# TensoSensor.net
KiCad netlist of a schematic drawn in Altium Designer
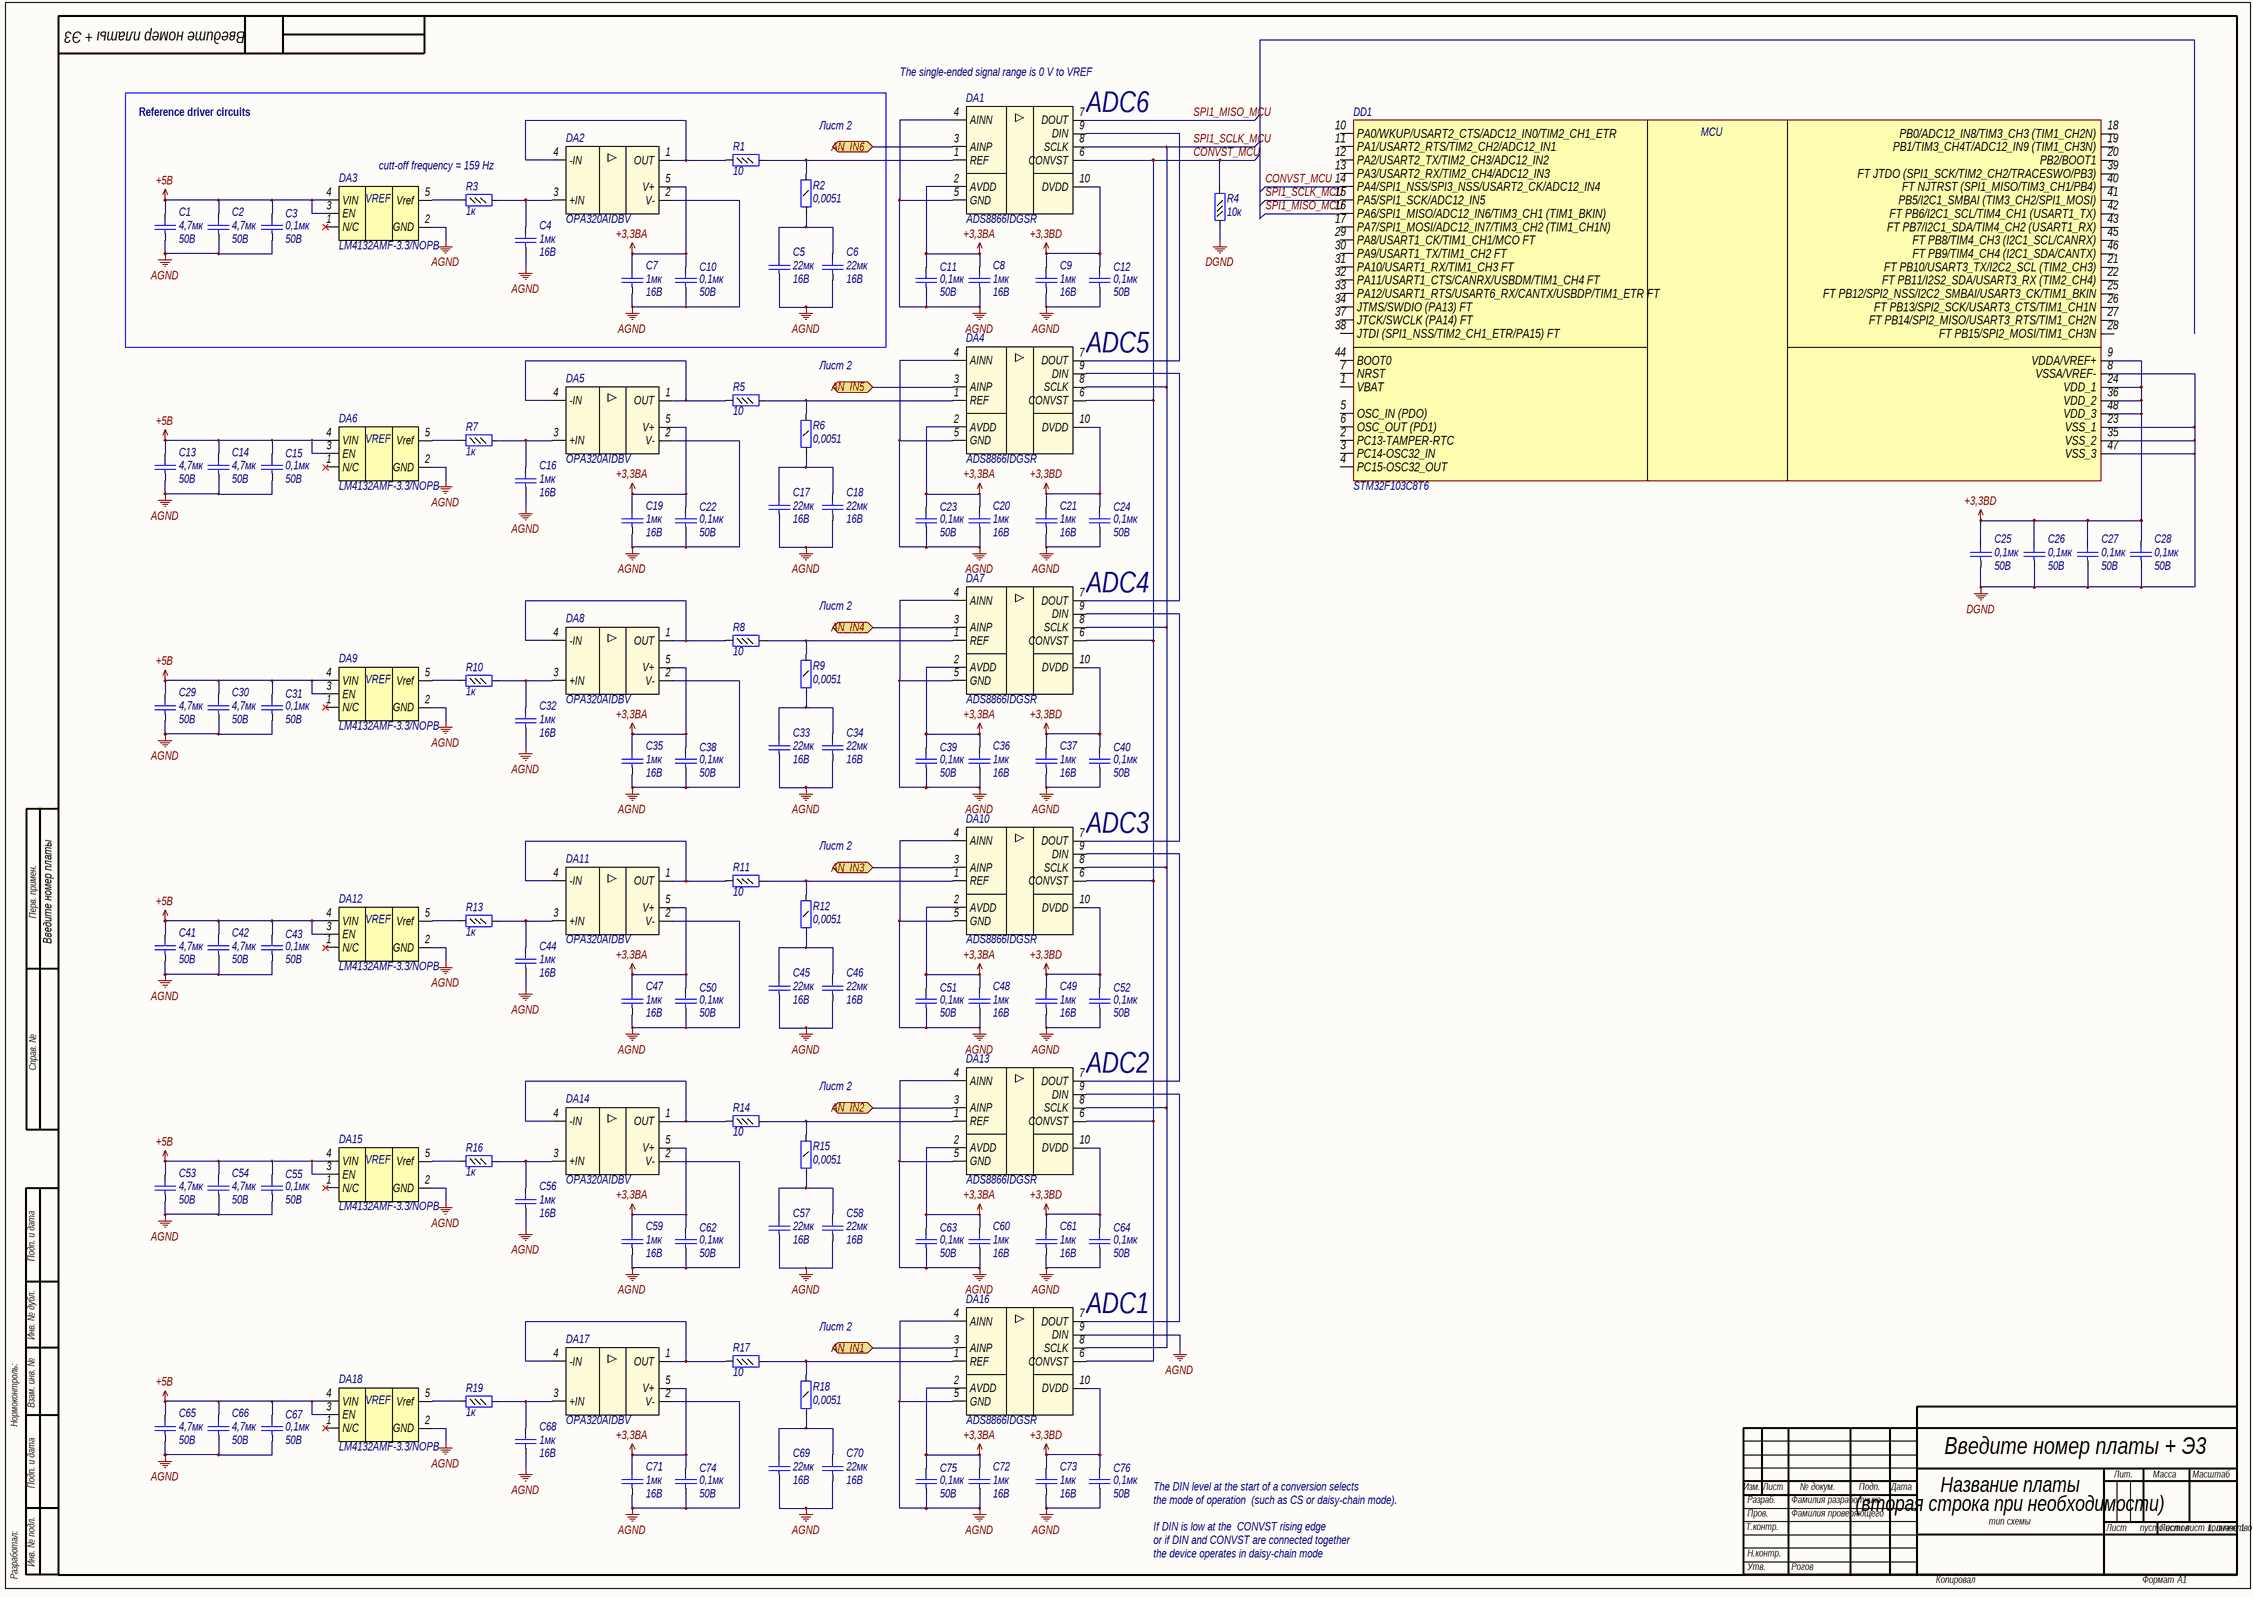
[diagram p0: TensoSensor.SchDoc]

(export (version "E")
  (design (tool "Eeschema 10.0.6"))
  (components
    (comp (ref "C1")
      (value "4,7мк")
      (footprint "C0805")
      (description "Конденсатор")
      (fields (field (name "VOLTAGE") "50В") (field (name "PART NUMBER") "GRM21BZ71H475KE15L"))
      (libsource (lib "MOP44") (part "Capacitor"))
    )
    (comp (ref "C2")
      (value "4,7мк")
      (footprint "C0805")
      (description "Конденсатор")
      (fields (field (name "VOLTAGE") "50В") (field (name "PART NUMBER") "GRM21BZ71H475KE15L"))
      (libsource (lib "MOP44") (part "Capacitor"))
    )
    (comp (ref "C3")
      (value "0,1мк")
      (footprint "C0603")
      (description "Конденсатор")
      (fields (field (name "VOLTAGE") "50B") (field (name "PART NUMBER") "GRM188R71H104KA93D"))
      (libsource (lib "MOP44") (part "Capacitor"))
    )
    (comp (ref "C4")
      (value "1мк")
      (footprint "C0603")
      (description "Конденсатор")
      (fields (field (name "VOLTAGE") "16B") (field (name "PART NUMBER") "GRM188R71C105KA12D**"))
      (libsource (lib "MOP44") (part "Capacitor"))
    )
    (comp (ref "C5")
      (value "22мк")
      (footprint "C1210")
      (description "Конденсатор")
      (fields (field (name "VOLTAGE") "16B") (field (name "PART NUMBER") "C3225X7R1C226M"))
      (libsource (lib "MOP44") (part "Capacitor"))
    )
    (comp (ref "C6")
      (value "22мк")
      (footprint "C1210")
      (description "Конденсатор")
      (fields (field (name "VOLTAGE") "16B") (field (name "PART NUMBER") "C3225X7R1C226M"))
      (libsource (lib "MOP44") (part "Capacitor"))
    )
    (comp (ref "C7")
      (value "1мк")
      (footprint "C0603")
      (description "Конденсатор")
      (fields (field (name "VOLTAGE") "16B") (field (name "PART NUMBER") "GRM188R71C105KA12D**"))
      (libsource (lib "MOP44") (part "Capacitor"))
    )
    (comp (ref "C8")
      (value "1мк")
      (footprint "C0603")
      (description "Конденсатор")
      (fields (field (name "VOLTAGE") "16B") (field (name "PART NUMBER") "GRM188R71C105KA12D**"))
      (libsource (lib "MOP44") (part "Capacitor"))
    )
    (comp (ref "C9")
      (value "1мк")
      (footprint "C0603")
      (description "Конденсатор")
      (fields (field (name "VOLTAGE") "16B") (field (name "PART NUMBER") "GRM188R71C105KA12D**"))
      (libsource (lib "MOP44") (part "Capacitor"))
    )
    (comp (ref "C10")
      (value "0,1мк")
      (footprint "C0603")
      (description "Конденсатор")
      (fields (field (name "VOLTAGE") "50B") (field (name "PART NUMBER") "GRM188R71H104KA93D"))
      (libsource (lib "MOP44") (part "Capacitor"))
    )
    (comp (ref "C11")
      (value "0,1мк")
      (footprint "C0603")
      (description "Конденсатор")
      (fields (field (name "VOLTAGE") "50B") (field (name "PART NUMBER") "GRM188R71H104KA93D"))
      (libsource (lib "MOP44") (part "Capacitor"))
    )
    (comp (ref "C12")
      (value "0,1мк")
      (footprint "C0603")
      (description "Конденсатор")
      (fields (field (name "VOLTAGE") "50B") (field (name "PART NUMBER") "GRM188R71H104KA93D"))
      (libsource (lib "MOP44") (part "Capacitor"))
    )
    (comp (ref "C13")
      (value "4,7мк")
      (footprint "C0805")
      (description "Конденсатор")
      (fields (field (name "VOLTAGE") "50В") (field (name "PART NUMBER") "GRM21BZ71H475KE15L"))
      (libsource (lib "MOP44") (part "Capacitor"))
    )
    (comp (ref "C14")
      (value "4,7мк")
      (footprint "C0805")
      (description "Конденсатор")
      (fields (field (name "VOLTAGE") "50В") (field (name "PART NUMBER") "GRM21BZ71H475KE15L"))
      (libsource (lib "MOP44") (part "Capacitor"))
    )
    (comp (ref "C15")
      (value "0,1мк")
      (footprint "C0603")
      (description "Конденсатор")
      (fields (field (name "VOLTAGE") "50B") (field (name "PART NUMBER") "GRM188R71H104KA93D"))
      (libsource (lib "MOP44") (part "Capacitor"))
    )
    (comp (ref "C16")
      (value "1мк")
      (footprint "C0603")
      (description "Конденсатор")
      (fields (field (name "VOLTAGE") "16B") (field (name "PART NUMBER") "GRM188R71C105KA12D**"))
      (libsource (lib "MOP44") (part "Capacitor"))
    )
    (comp (ref "C17")
      (value "22мк")
      (footprint "C1210")
      (description "Конденсатор")
      (fields (field (name "VOLTAGE") "16B") (field (name "PART NUMBER") "C3225X7R1C226M"))
      (libsource (lib "MOP44") (part "Capacitor"))
    )
    (comp (ref "C18")
      (value "22мк")
      (footprint "C1210")
      (description "Конденсатор")
      (fields (field (name "VOLTAGE") "16B") (field (name "PART NUMBER") "C3225X7R1C226M"))
      (libsource (lib "MOP44") (part "Capacitor"))
    )
    (comp (ref "C19")
      (value "1мк")
      (footprint "C0603")
      (description "Конденсатор")
      (fields (field (name "VOLTAGE") "16B") (field (name "PART NUMBER") "GRM188R71C105KA12D**"))
      (libsource (lib "MOP44") (part "Capacitor"))
    )
    (comp (ref "C20")
      (value "1мк")
      (footprint "C0603")
      (description "Конденсатор")
      (fields (field (name "VOLTAGE") "16B") (field (name "PART NUMBER") "GRM188R71C105KA12D**"))
      (libsource (lib "MOP44") (part "Capacitor"))
    )
    (comp (ref "C21")
      (value "1мк")
      (footprint "C0603")
      (description "Конденсатор")
      (fields (field (name "VOLTAGE") "16B") (field (name "PART NUMBER") "GRM188R71C105KA12D**"))
      (libsource (lib "MOP44") (part "Capacitor"))
    )
    (comp (ref "C22")
      (value "0,1мк")
      (footprint "C0603")
      (description "Конденсатор")
      (fields (field (name "VOLTAGE") "50B") (field (name "PART NUMBER") "GRM188R71H104KA93D"))
      (libsource (lib "MOP44") (part "Capacitor"))
    )
    (comp (ref "C23")
      (value "0,1мк")
      (footprint "C0603")
      (description "Конденсатор")
      (fields (field (name "VOLTAGE") "50B") (field (name "PART NUMBER") "GRM188R71H104KA93D"))
      (libsource (lib "MOP44") (part "Capacitor"))
    )
    (comp (ref "C24")
      (value "0,1мк")
      (footprint "C0603")
      (description "Конденсатор")
      (fields (field (name "VOLTAGE") "50B") (field (name "PART NUMBER") "GRM188R71H104KA93D"))
      (libsource (lib "MOP44") (part "Capacitor"))
    )
    (comp (ref "C25")
      (value "0,1мк")
      (footprint "C0603")
      (description "Конденсатор")
      (fields (field (name "VOLTAGE") "50B") (field (name "PART NUMBER") "GRM188R71H104KA93D"))
      (libsource (lib "MOP44") (part "Capacitor"))
    )
    (comp (ref "C26")
      (value "0,1мк")
      (footprint "C0603")
      (description "Конденсатор")
      (fields (field (name "VOLTAGE") "50B") (field (name "PART NUMBER") "GRM188R71H104KA93D"))
      (libsource (lib "MOP44") (part "Capacitor"))
    )
    (comp (ref "C27")
      (value "0,1мк")
      (footprint "C0603")
      (description "Конденсатор")
      (fields (field (name "VOLTAGE") "50B") (field (name "PART NUMBER") "GRM188R71H104KA93D"))
      (libsource (lib "MOP44") (part "Capacitor"))
    )
    (comp (ref "C28")
      (value "0,1мк")
      (footprint "C0603")
      (description "Конденсатор")
      (fields (field (name "VOLTAGE") "50B") (field (name "PART NUMBER") "GRM188R71H104KA93D"))
      (libsource (lib "MOP44") (part "Capacitor"))
    )
    (comp (ref "C29")
      (value "4,7мк")
      (footprint "C0805")
      (description "Конденсатор")
      (fields (field (name "VOLTAGE") "50В") (field (name "PART NUMBER") "GRM21BZ71H475KE15L"))
      (libsource (lib "MOP44") (part "Capacitor"))
    )
    (comp (ref "C30")
      (value "4,7мк")
      (footprint "C0805")
      (description "Конденсатор")
      (fields (field (name "VOLTAGE") "50В") (field (name "PART NUMBER") "GRM21BZ71H475KE15L"))
      (libsource (lib "MOP44") (part "Capacitor"))
    )
    (comp (ref "C31")
      (value "0,1мк")
      (footprint "C0603")
      (description "Конденсатор")
      (fields (field (name "VOLTAGE") "50B") (field (name "PART NUMBER") "GRM188R71H104KA93D"))
      (libsource (lib "MOP44") (part "Capacitor"))
    )
    (comp (ref "C32")
      (value "1мк")
      (footprint "C0603")
      (description "Конденсатор")
      (fields (field (name "VOLTAGE") "16B") (field (name "PART NUMBER") "GRM188R71C105KA12D**"))
      (libsource (lib "MOP44") (part "Capacitor"))
    )
    (comp (ref "C33")
      (value "22мк")
      (footprint "C1210")
      (description "Конденсатор")
      (fields (field (name "VOLTAGE") "16B") (field (name "PART NUMBER") "C3225X7R1C226M"))
      (libsource (lib "MOP44") (part "Capacitor"))
    )
    (comp (ref "C34")
      (value "22мк")
      (footprint "C1210")
      (description "Конденсатор")
      (fields (field (name "VOLTAGE") "16B") (field (name "PART NUMBER") "C3225X7R1C226M"))
      (libsource (lib "MOP44") (part "Capacitor"))
    )
    (comp (ref "C35")
      (value "1мк")
      (footprint "C0603")
      (description "Конденсатор")
      (fields (field (name "VOLTAGE") "16B") (field (name "PART NUMBER") "GRM188R71C105KA12D**"))
      (libsource (lib "MOP44") (part "Capacitor"))
    )
    (comp (ref "C36")
      (value "1мк")
      (footprint "C0603")
      (description "Конденсатор")
      (fields (field (name "VOLTAGE") "16B") (field (name "PART NUMBER") "GRM188R71C105KA12D**"))
      (libsource (lib "MOP44") (part "Capacitor"))
    )
    (comp (ref "C37")
      (value "1мк")
      (footprint "C0603")
      (description "Конденсатор")
      (fields (field (name "VOLTAGE") "16B") (field (name "PART NUMBER") "GRM188R71C105KA12D**"))
      (libsource (lib "MOP44") (part "Capacitor"))
    )
    (comp (ref "C38")
      (value "0,1мк")
      (footprint "C0603")
      (description "Конденсатор")
      (fields (field (name "VOLTAGE") "50B") (field (name "PART NUMBER") "GRM188R71H104KA93D"))
      (libsource (lib "MOP44") (part "Capacitor"))
    )
    (comp (ref "C39")
      (value "0,1мк")
      (footprint "C0603")
      (description "Конденсатор")
      (fields (field (name "VOLTAGE") "50B") (field (name "PART NUMBER") "GRM188R71H104KA93D"))
      (libsource (lib "MOP44") (part "Capacitor"))
    )
    (comp (ref "C40")
      (value "0,1мк")
      (footprint "C0603")
      (description "Конденсатор")
      (fields (field (name "VOLTAGE") "50B") (field (name "PART NUMBER") "GRM188R71H104KA93D"))
      (libsource (lib "MOP44") (part "Capacitor"))
    )
    (comp (ref "C41")
      (value "4,7мк")
      (footprint "C0805")
      (description "Конденсатор")
      (fields (field (name "VOLTAGE") "50В") (field (name "PART NUMBER") "GRM21BZ71H475KE15L"))
      (libsource (lib "MOP44") (part "Capacitor"))
    )
    (comp (ref "C42")
      (value "4,7мк")
      (footprint "C0805")
      (description "Конденсатор")
      (fields (field (name "VOLTAGE") "50В") (field (name "PART NUMBER") "GRM21BZ71H475KE15L"))
      (libsource (lib "MOP44") (part "Capacitor"))
    )
    (comp (ref "C43")
      (value "0,1мк")
      (footprint "C0603")
      (description "Конденсатор")
      (fields (field (name "VOLTAGE") "50B") (field (name "PART NUMBER") "GRM188R71H104KA93D"))
      (libsource (lib "MOP44") (part "Capacitor"))
    )
    (comp (ref "C44")
      (value "1мк")
      (footprint "C0603")
      (description "Конденсатор")
      (fields (field (name "VOLTAGE") "16B") (field (name "PART NUMBER") "GRM188R71C105KA12D**"))
      (libsource (lib "MOP44") (part "Capacitor"))
    )
    (comp (ref "C45")
      (value "22мк")
      (footprint "C1210")
      (description "Конденсатор")
      (fields (field (name "VOLTAGE") "16B") (field (name "PART NUMBER") "C3225X7R1C226M"))
      (libsource (lib "MOP44") (part "Capacitor"))
    )
    (comp (ref "C46")
      (value "22мк")
      (footprint "C1210")
      (description "Конденсатор")
      (fields (field (name "VOLTAGE") "16B") (field (name "PART NUMBER") "C3225X7R1C226M"))
      (libsource (lib "MOP44") (part "Capacitor"))
    )
    (comp (ref "C47")
      (value "1мк")
      (footprint "C0603")
      (description "Конденсатор")
      (fields (field (name "VOLTAGE") "16B") (field (name "PART NUMBER") "GRM188R71C105KA12D**"))
      (libsource (lib "MOP44") (part "Capacitor"))
    )
    (comp (ref "C48")
      (value "1мк")
      (footprint "C0603")
      (description "Конденсатор")
      (fields (field (name "VOLTAGE") "16B") (field (name "PART NUMBER") "GRM188R71C105KA12D**"))
      (libsource (lib "MOP44") (part "Capacitor"))
    )
    (comp (ref "C49")
      (value "1мк")
      (footprint "C0603")
      (description "Конденсатор")
      (fields (field (name "VOLTAGE") "16B") (field (name "PART NUMBER") "GRM188R71C105KA12D**"))
      (libsource (lib "MOP44") (part "Capacitor"))
    )
    (comp (ref "C50")
      (value "0,1мк")
      (footprint "C0603")
      (description "Конденсатор")
      (fields (field (name "VOLTAGE") "50B") (field (name "PART NUMBER") "GRM188R71H104KA93D"))
      (libsource (lib "MOP44") (part "Capacitor"))
    )
    (comp (ref "C51")
      (value "0,1мк")
      (footprint "C0603")
      (description "Конденсатор")
      (fields (field (name "VOLTAGE") "50B") (field (name "PART NUMBER") "GRM188R71H104KA93D"))
      (libsource (lib "MOP44") (part "Capacitor"))
    )
    (comp (ref "C52")
      (value "0,1мк")
      (footprint "C0603")
      (description "Конденсатор")
      (fields (field (name "VOLTAGE") "50B") (field (name "PART NUMBER") "GRM188R71H104KA93D"))
      (libsource (lib "MOP44") (part "Capacitor"))
    )
    (comp (ref "C53")
      (value "4,7мк")
      (footprint "C0805")
      (description "Конденсатор")
      (fields (field (name "VOLTAGE") "50В") (field (name "PART NUMBER") "GRM21BZ71H475KE15L"))
      (libsource (lib "MOP44") (part "Capacitor"))
    )
    (comp (ref "C54")
      (value "4,7мк")
      (footprint "C0805")
      (description "Конденсатор")
      (fields (field (name "VOLTAGE") "50В") (field (name "PART NUMBER") "GRM21BZ71H475KE15L"))
      (libsource (lib "MOP44") (part "Capacitor"))
    )
    (comp (ref "C55")
      (value "0,1мк")
      (footprint "C0603")
      (description "Конденсатор")
      (fields (field (name "VOLTAGE") "50B") (field (name "PART NUMBER") "GRM188R71H104KA93D"))
      (libsource (lib "MOP44") (part "Capacitor"))
    )
    (comp (ref "C56")
      (value "1мк")
      (footprint "C0603")
      (description "Конденсатор")
      (fields (field (name "VOLTAGE") "16B") (field (name "PART NUMBER") "GRM188R71C105KA12D**"))
      (libsource (lib "MOP44") (part "Capacitor"))
    )
    (comp (ref "C57")
      (value "22мк")
      (footprint "C1210")
      (description "Конденсатор")
      (fields (field (name "VOLTAGE") "16B") (field (name "PART NUMBER") "C3225X7R1C226M"))
      (libsource (lib "MOP44") (part "Capacitor"))
    )
    (comp (ref "C58")
      (value "22мк")
      (footprint "C1210")
      (description "Конденсатор")
      (fields (field (name "VOLTAGE") "16B") (field (name "PART NUMBER") "C3225X7R1C226M"))
      (libsource (lib "MOP44") (part "Capacitor"))
    )
    (comp (ref "C59")
      (value "1мк")
      (footprint "C0603")
      (description "Конденсатор")
      (fields (field (name "VOLTAGE") "16B") (field (name "PART NUMBER") "GRM188R71C105KA12D**"))
      (libsource (lib "MOP44") (part "Capacitor"))
    )
    (comp (ref "C60")
      (value "1мк")
      (footprint "C0603")
      (description "Конденсатор")
      (fields (field (name "VOLTAGE") "16B") (field (name "PART NUMBER") "GRM188R71C105KA12D**"))
      (libsource (lib "MOP44") (part "Capacitor"))
    )
    (comp (ref "C61")
      (value "1мк")
      (footprint "C0603")
      (description "Конденсатор")
      (fields (field (name "VOLTAGE") "16B") (field (name "PART NUMBER") "GRM188R71C105KA12D**"))
      (libsource (lib "MOP44") (part "Capacitor"))
    )
    (comp (ref "C62")
      (value "0,1мк")
      (footprint "C0603")
      (description "Конденсатор")
      (fields (field (name "VOLTAGE") "50B") (field (name "PART NUMBER") "GRM188R71H104KA93D"))
      (libsource (lib "MOP44") (part "Capacitor"))
    )
    (comp (ref "C63")
      (value "0,1мк")
      (footprint "C0603")
      (description "Конденсатор")
      (fields (field (name "VOLTAGE") "50B") (field (name "PART NUMBER") "GRM188R71H104KA93D"))
      (libsource (lib "MOP44") (part "Capacitor"))
    )
    (comp (ref "C64")
      (value "0,1мк")
      (footprint "C0603")
      (description "Конденсатор")
      (fields (field (name "VOLTAGE") "50B") (field (name "PART NUMBER") "GRM188R71H104KA93D"))
      (libsource (lib "MOP44") (part "Capacitor"))
    )
    (comp (ref "C65")
      (value "4,7мк")
      (footprint "C0805")
      (description "Конденсатор")
      (fields (field (name "VOLTAGE") "50В") (field (name "PART NUMBER") "GRM21BZ71H475KE15L"))
      (libsource (lib "MOP44") (part "Capacitor"))
    )
    (comp (ref "C66")
      (value "4,7мк")
      (footprint "C0805")
      (description "Конденсатор")
      (fields (field (name "VOLTAGE") "50В") (field (name "PART NUMBER") "GRM21BZ71H475KE15L"))
      (libsource (lib "MOP44") (part "Capacitor"))
    )
    (comp (ref "C67")
      (value "0,1мк")
      (footprint "C0603")
      (description "Конденсатор")
      (fields (field (name "VOLTAGE") "50B") (field (name "PART NUMBER") "GRM188R71H104KA93D"))
      (libsource (lib "MOP44") (part "Capacitor"))
    )
    (comp (ref "C68")
      (value "1мк")
      (footprint "C0603")
      (description "Конденсатор")
      (fields (field (name "VOLTAGE") "16B") (field (name "PART NUMBER") "GRM188R71C105KA12D**"))
      (libsource (lib "MOP44") (part "Capacitor"))
    )
    (comp (ref "C69")
      (value "22мк")
      (footprint "C1210")
      (description "Конденсатор")
      (fields (field (name "VOLTAGE") "16B") (field (name "PART NUMBER") "C3225X7R1C226M"))
      (libsource (lib "MOP44") (part "Capacitor"))
    )
    (comp (ref "C70")
      (value "22мк")
      (footprint "C1210")
      (description "Конденсатор")
      (fields (field (name "VOLTAGE") "16B") (field (name "PART NUMBER") "C3225X7R1C226M"))
      (libsource (lib "MOP44") (part "Capacitor"))
    )
    (comp (ref "C71")
      (value "1мк")
      (footprint "C0603")
      (description "Конденсатор")
      (fields (field (name "VOLTAGE") "16B") (field (name "PART NUMBER") "GRM188R71C105KA12D**"))
      (libsource (lib "MOP44") (part "Capacitor"))
    )
    (comp (ref "C72")
      (value "1мк")
      (footprint "C0603")
      (description "Конденсатор")
      (fields (field (name "VOLTAGE") "16B") (field (name "PART NUMBER") "GRM188R71C105KA12D**"))
      (libsource (lib "MOP44") (part "Capacitor"))
    )
    (comp (ref "C73")
      (value "1мк")
      (footprint "C0603")
      (description "Конденсатор")
      (fields (field (name "VOLTAGE") "16B") (field (name "PART NUMBER") "GRM188R71C105KA12D**"))
      (libsource (lib "MOP44") (part "Capacitor"))
    )
    (comp (ref "C74")
      (value "0,1мк")
      (footprint "C0603")
      (description "Конденсатор")
      (fields (field (name "VOLTAGE") "50B") (field (name "PART NUMBER") "GRM188R71H104KA93D"))
      (libsource (lib "MOP44") (part "Capacitor"))
    )
    (comp (ref "C75")
      (value "0,1мк")
      (footprint "C0603")
      (description "Конденсатор")
      (fields (field (name "VOLTAGE") "50B") (field (name "PART NUMBER") "GRM188R71H104KA93D"))
      (libsource (lib "MOP44") (part "Capacitor"))
    )
    (comp (ref "C76")
      (value "0,1мк")
      (footprint "C0603")
      (description "Конденсатор")
      (fields (field (name "VOLTAGE") "50B") (field (name "PART NUMBER") "GRM188R71H104KA93D"))
      (libsource (lib "MOP44") (part "Capacitor"))
    )
    (comp (ref "DA1")
      (value "ADS8866")
      (footprint "MSOP10")
      (description "100-kSPS, serial interface, micropower, miniature,  single-ended input, SAR")
      (fields (field (name "PART NUMBER") "ADS8866IDGSR"))
      (libsource (lib "MOP44") (part "ADS8866"))
    )
    (comp (ref "DA2")
      (value "OPA320")
      (footprint "SOT23-5")
      (description "Precision, 20-MHz, 0.9-pA, Low-Noise, RRIO")
      (fields (field (name "PART NUMBER") "OPA320AIDBV"))
      (libsource (lib "MOP44") (part "OPA320"))
    )
    (comp (ref "DA3")
      (value "LM4132")
      (footprint "SOT23-5")
      (description "Precision Low Dropout Voltage Reference")
      (fields
        (field (name "PART NUMBER") "LM4132AMF-3.3/NOPB")
        (field (name "MANUFACTURER") "Texas Instruments")
      )
      (libsource (lib "MOP44") (part "LM4132"))
    )
    (comp (ref "DA4")
      (value "ADS8866")
      (footprint "MSOP10")
      (description "100-kSPS, serial interface, micropower, miniature,  single-ended input, SAR")
      (fields (field (name "PART NUMBER") "ADS8866IDGSR"))
      (libsource (lib "MOP44") (part "ADS8866"))
    )
    (comp (ref "DA5")
      (value "OPA320")
      (footprint "SOT23-5")
      (description "Precision, 20-MHz, 0.9-pA, Low-Noise, RRIO")
      (fields (field (name "PART NUMBER") "OPA320AIDBV"))
      (libsource (lib "MOP44") (part "OPA320"))
    )
    (comp (ref "DA6")
      (value "LM4132")
      (footprint "SOT23-5")
      (description "Precision Low Dropout Voltage Reference")
      (fields
        (field (name "PART NUMBER") "LM4132AMF-3.3/NOPB")
        (field (name "MANUFACTURER") "Texas Instruments")
      )
      (libsource (lib "MOP44") (part "LM4132"))
    )
    (comp (ref "DA7")
      (value "ADS8866")
      (footprint "MSOP10")
      (description "100-kSPS, serial interface, micropower, miniature,  single-ended input, SAR")
      (fields (field (name "PART NUMBER") "ADS8866IDGSR"))
      (libsource (lib "MOP44") (part "ADS8866"))
    )
    (comp (ref "DA8")
      (value "OPA320")
      (footprint "SOT23-5")
      (description "Precision, 20-MHz, 0.9-pA, Low-Noise, RRIO")
      (fields (field (name "PART NUMBER") "OPA320AIDBV"))
      (libsource (lib "MOP44") (part "OPA320"))
    )
    (comp (ref "DA9")
      (value "LM4132")
      (footprint "SOT23-5")
      (description "Precision Low Dropout Voltage Reference")
      (fields
        (field (name "PART NUMBER") "LM4132AMF-3.3/NOPB")
        (field (name "MANUFACTURER") "Texas Instruments")
      )
      (libsource (lib "MOP44") (part "LM4132"))
    )
    (comp (ref "DA10")
      (value "ADS8866")
      (footprint "MSOP10")
      (description "100-kSPS, serial interface, micropower, miniature,  single-ended input, SAR")
      (fields (field (name "PART NUMBER") "ADS8866IDGSR"))
      (libsource (lib "MOP44") (part "ADS8866"))
    )
    (comp (ref "DA11")
      (value "OPA320")
      (footprint "SOT23-5")
      (description "Precision, 20-MHz, 0.9-pA, Low-Noise, RRIO")
      (fields (field (name "PART NUMBER") "OPA320AIDBV"))
      (libsource (lib "MOP44") (part "OPA320"))
    )
    (comp (ref "DA12")
      (value "LM4132")
      (footprint "SOT23-5")
      (description "Precision Low Dropout Voltage Reference")
      (fields
        (field (name "PART NUMBER") "LM4132AMF-3.3/NOPB")
        (field (name "MANUFACTURER") "Texas Instruments")
      )
      (libsource (lib "MOP44") (part "LM4132"))
    )
    (comp (ref "DA13")
      (value "ADS8866")
      (footprint "MSOP10")
      (description "100-kSPS, serial interface, micropower, miniature,  single-ended input, SAR")
      (fields (field (name "PART NUMBER") "ADS8866IDGSR"))
      (libsource (lib "MOP44") (part "ADS8866"))
    )
    (comp (ref "DA14")
      (value "OPA320")
      (footprint "SOT23-5")
      (description "Precision, 20-MHz, 0.9-pA, Low-Noise, RRIO")
      (fields (field (name "PART NUMBER") "OPA320AIDBV"))
      (libsource (lib "MOP44") (part "OPA320"))
    )
    (comp (ref "DA15")
      (value "LM4132")
      (footprint "SOT23-5")
      (description "Precision Low Dropout Voltage Reference")
      (fields
        (field (name "PART NUMBER") "LM4132AMF-3.3/NOPB")
        (field (name "MANUFACTURER") "Texas Instruments")
      )
      (libsource (lib "MOP44") (part "LM4132"))
    )
    (comp (ref "DA16")
      (value "ADS8866")
      (footprint "MSOP10")
      (description "100-kSPS, serial interface, micropower, miniature,  single-ended input, SAR")
      (fields (field (name "PART NUMBER") "ADS8866IDGSR"))
      (libsource (lib "MOP44") (part "ADS8866"))
    )
    (comp (ref "DA17")
      (value "OPA320")
      (footprint "SOT23-5")
      (description "Precision, 20-MHz, 0.9-pA, Low-Noise, RRIO")
      (fields (field (name "PART NUMBER") "OPA320AIDBV"))
      (libsource (lib "MOP44") (part "OPA320"))
    )
    (comp (ref "DA18")
      (value "LM4132")
      (footprint "SOT23-5")
      (description "Precision Low Dropout Voltage Reference")
      (fields
        (field (name "PART NUMBER") "LM4132AMF-3.3/NOPB")
        (field (name "MANUFACTURER") "Texas Instruments")
      )
      (libsource (lib "MOP44") (part "LM4132"))
    )
    (comp (ref "DD1")
      (value "STM32F103C8T6")
      (footprint "LQFP48")
      (libsource (lib "MOP44") (part "STM32F103C8T6"))
    )
    (comp (ref "R1")
      (value "10")
      (footprint "R0603")
      (description "Резистор")
      (fields (field (name "PART NUMBER") "RC0603FR-0710RL") (field (name "POWER") "0,062Вт"))
      (libsource (lib "MOP44") (part "Resistor_0,062Вт"))
    )
    (comp (ref "R2")
      (value "0,0051")
      (footprint "R1206")
      (description "Резистор")
      (fields (field (name "PART NUMBER") "RC1206JR-075M1L") (field (name "POWER") "0,25Вт"))
      (libsource (lib "MOP44") (part "Resistor_0,25Вт"))
    )
    (comp (ref "R3")
      (value "1к")
      (footprint "R0603")
      (description "Резистор")
      (fields (field (name "PART NUMBER") "RC0603FR-071KL") (field (name "POWER") "0,062Вт"))
      (libsource (lib "MOP44") (part "Resistor_0,062Вт"))
    )
    (comp (ref "R4")
      (value "10к")
      (footprint "R0603")
      (description "Резистор")
      (fields (field (name "PART NUMBER") "RC0603FR-0710KL") (field (name "POWER") "0,062Вт"))
      (libsource (lib "") (part "Resistor_0,062Вт_1"))
    )
    (comp (ref "R5")
      (value "10")
      (footprint "R0603")
      (description "Резистор")
      (fields (field (name "PART NUMBER") "RC0603FR-0710RL") (field (name "POWER") "0,062Вт"))
      (libsource (lib "MOP44") (part "Resistor_0,062Вт"))
    )
    (comp (ref "R6")
      (value "0,0051")
      (footprint "R1206")
      (description "Резистор")
      (fields (field (name "PART NUMBER") "RC1206JR-075M1L") (field (name "POWER") "0,25Вт"))
      (libsource (lib "MOP44") (part "Resistor_0,25Вт"))
    )
    (comp (ref "R7")
      (value "1к")
      (footprint "R0603")
      (description "Резистор")
      (fields (field (name "PART NUMBER") "RC0603FR-071KL") (field (name "POWER") "0,062Вт"))
      (libsource (lib "MOP44") (part "Resistor_0,062Вт"))
    )
    (comp (ref "R8")
      (value "10")
      (footprint "R0603")
      (description "Резистор")
      (fields (field (name "PART NUMBER") "RC0603FR-0710RL") (field (name "POWER") "0,062Вт"))
      (libsource (lib "MOP44") (part "Resistor_0,062Вт"))
    )
    (comp (ref "R9")
      (value "0,0051")
      (footprint "R1206")
      (description "Резистор")
      (fields (field (name "PART NUMBER") "RC1206JR-075M1L") (field (name "POWER") "0,25Вт"))
      (libsource (lib "MOP44") (part "Resistor_0,25Вт"))
    )
    (comp (ref "R10")
      (value "1к")
      (footprint "R0603")
      (description "Резистор")
      (fields (field (name "PART NUMBER") "RC0603FR-071KL") (field (name "POWER") "0,062Вт"))
      (libsource (lib "MOP44") (part "Resistor_0,062Вт"))
    )
    (comp (ref "R11")
      (value "10")
      (footprint "R0603")
      (description "Резистор")
      (fields (field (name "PART NUMBER") "RC0603FR-0710RL") (field (name "POWER") "0,062Вт"))
      (libsource (lib "MOP44") (part "Resistor_0,062Вт"))
    )
    (comp (ref "R12")
      (value "0,0051")
      (footprint "R1206")
      (description "Резистор")
      (fields (field (name "PART NUMBER") "RC1206JR-075M1L") (field (name "POWER") "0,25Вт"))
      (libsource (lib "MOP44") (part "Resistor_0,25Вт"))
    )
    (comp (ref "R13")
      (value "1к")
      (footprint "R0603")
      (description "Резистор")
      (fields (field (name "PART NUMBER") "RC0603FR-071KL") (field (name "POWER") "0,062Вт"))
      (libsource (lib "MOP44") (part "Resistor_0,062Вт"))
    )
    (comp (ref "R14")
      (value "10")
      (footprint "R0603")
      (description "Резистор")
      (fields (field (name "PART NUMBER") "RC0603FR-0710RL") (field (name "POWER") "0,062Вт"))
      (libsource (lib "MOP44") (part "Resistor_0,062Вт"))
    )
    (comp (ref "R15")
      (value "0,0051")
      (footprint "R1206")
      (description "Резистор")
      (fields (field (name "PART NUMBER") "RC1206JR-075M1L") (field (name "POWER") "0,25Вт"))
      (libsource (lib "MOP44") (part "Resistor_0,25Вт"))
    )
    (comp (ref "R16")
      (value "1к")
      (footprint "R0603")
      (description "Резистор")
      (fields (field (name "PART NUMBER") "RC0603FR-071KL") (field (name "POWER") "0,062Вт"))
      (libsource (lib "MOP44") (part "Resistor_0,062Вт"))
    )
    (comp (ref "R17")
      (value "10")
      (footprint "R0603")
      (description "Резистор")
      (fields (field (name "PART NUMBER") "RC0603FR-0710RL") (field (name "POWER") "0,062Вт"))
      (libsource (lib "MOP44") (part "Resistor_0,062Вт"))
    )
    (comp (ref "R18")
      (value "0,0051")
      (footprint "R1206")
      (description "Резистор")
      (fields (field (name "PART NUMBER") "RC1206JR-075M1L") (field (name "POWER") "0,25Вт"))
      (libsource (lib "MOP44") (part "Resistor_0,25Вт"))
    )
    (comp (ref "R19")
      (value "1к")
      (footprint "R0603")
      (description "Резистор")
      (fields (field (name "PART NUMBER") "RC0603FR-071KL") (field (name "POWER") "0,062Вт"))
      (libsource (lib "MOP44") (part "Resistor_0,062Вт"))
    )
  )
  (nets
    (net (code "1") (name "+3,3BA") (class "Default")
      (node (ref "C10") (pin "2") (pinfunction "2_2") (pintype "passive"))
      (node (ref "C11") (pin "2") (pinfunction "2_2") (pintype "passive"))
      (node (ref "C19") (pin "2") (pinfunction "2_2") (pintype "passive"))
      (node (ref "C20") (pin "2") (pinfunction "2_2") (pintype "passive"))
      (node (ref "C22") (pin "2") (pinfunction "2_2") (pintype "passive"))
      (node (ref "C23") (pin "2") (pinfunction "2_2") (pintype "passive"))
      (node (ref "C35") (pin "2") (pinfunction "2_2") (pintype "passive"))
      (node (ref "C36") (pin "2") (pinfunction "2_2") (pintype "passive"))
      (node (ref "C38") (pin "2") (pinfunction "2_2") (pintype "passive"))
      (node (ref "C39") (pin "2") (pinfunction "2_2") (pintype "passive"))
      (node (ref "C47") (pin "2") (pinfunction "2_2") (pintype "passive"))
      (node (ref "C48") (pin "2") (pinfunction "2_2") (pintype "passive"))
      (node (ref "C50") (pin "2") (pinfunction "2_2") (pintype "passive"))
      (node (ref "C51") (pin "2") (pinfunction "2_2") (pintype "passive"))
      (node (ref "C59") (pin "2") (pinfunction "2_2") (pintype "passive"))
      (node (ref "C60") (pin "2") (pinfunction "2_2") (pintype "passive"))
      (node (ref "C62") (pin "2") (pinfunction "2_2") (pintype "passive"))
      (node (ref "C63") (pin "2") (pinfunction "2_2") (pintype "passive"))
      (node (ref "C7") (pin "2") (pinfunction "2_2") (pintype "passive"))
      (node (ref "C71") (pin "2") (pinfunction "2_2") (pintype "passive"))
      (node (ref "C72") (pin "2") (pinfunction "2_2") (pintype "passive"))
      (node (ref "C74") (pin "2") (pinfunction "2_2") (pintype "passive"))
      (node (ref "C75") (pin "2") (pinfunction "2_2") (pintype "passive"))
      (node (ref "C8") (pin "2") (pinfunction "2_2") (pintype "passive"))
      (node (ref "DA1") (pin "2") (pinfunction "AVDD_2") (pintype "passive"))
      (node (ref "DA10") (pin "2") (pinfunction "AVDD_2") (pintype "passive"))
      (node (ref "DA11") (pin "5") (pinfunction "V+_5") (pintype "passive"))
      (node (ref "DA13") (pin "2") (pinfunction "AVDD_2") (pintype "passive"))
      (node (ref "DA14") (pin "5") (pinfunction "V+_5") (pintype "passive"))
      (node (ref "DA16") (pin "2") (pinfunction "AVDD_2") (pintype "passive"))
      (node (ref "DA17") (pin "5") (pinfunction "V+_5") (pintype "passive"))
      (node (ref "DA2") (pin "5") (pinfunction "V+_5") (pintype "passive"))
      (node (ref "DA4") (pin "2") (pinfunction "AVDD_2") (pintype "passive"))
      (node (ref "DA5") (pin "5") (pinfunction "V+_5") (pintype "passive"))
      (node (ref "DA7") (pin "2") (pinfunction "AVDD_2") (pintype "passive"))
      (node (ref "DA8") (pin "5") (pinfunction "V+_5") (pintype "passive"))
    )
    (net (code "2") (name "+3,3BD") (class "Default")
      (node (ref "C12") (pin "2") (pinfunction "2_2") (pintype "passive"))
      (node (ref "C21") (pin "2") (pinfunction "2_2") (pintype "passive"))
      (node (ref "C24") (pin "2") (pinfunction "2_2") (pintype "passive"))
      (node (ref "C25") (pin "2") (pinfunction "2_2") (pintype "passive"))
      (node (ref "C26") (pin "2") (pinfunction "2_2") (pintype "passive"))
      (node (ref "C27") (pin "2") (pinfunction "2_2") (pintype "passive"))
      (node (ref "C28") (pin "2") (pinfunction "2_2") (pintype "passive"))
      (node (ref "C37") (pin "2") (pinfunction "2_2") (pintype "passive"))
      (node (ref "C40") (pin "2") (pinfunction "2_2") (pintype "passive"))
      (node (ref "C49") (pin "2") (pinfunction "2_2") (pintype "passive"))
      (node (ref "C52") (pin "2") (pinfunction "2_2") (pintype "passive"))
      (node (ref "C61") (pin "2") (pinfunction "2_2") (pintype "passive"))
      (node (ref "C64") (pin "2") (pinfunction "2_2") (pintype "passive"))
      (node (ref "C73") (pin "2") (pinfunction "2_2") (pintype "passive"))
      (node (ref "C76") (pin "2") (pinfunction "2_2") (pintype "passive"))
      (node (ref "C9") (pin "2") (pinfunction "2_2") (pintype "passive"))
      (node (ref "DA1") (pin "10") (pinfunction "DVDD_10") (pintype "passive"))
      (node (ref "DA10") (pin "10") (pinfunction "DVDD_10") (pintype "passive"))
      (node (ref "DA13") (pin "10") (pinfunction "DVDD_10") (pintype "passive"))
      (node (ref "DA16") (pin "10") (pinfunction "DVDD_10") (pintype "passive"))
      (node (ref "DA4") (pin "10") (pinfunction "DVDD_10") (pintype "passive"))
      (node (ref "DA7") (pin "10") (pinfunction "DVDD_10") (pintype "passive"))
      (node (ref "DD1") (pin "24") (pinfunction "VDD_1_24") (pintype "passive"))
      (node (ref "DD1") (pin "36") (pinfunction "VDD_2_36") (pintype "passive"))
      (node (ref "DD1") (pin "48") (pinfunction "VDD_3_48") (pintype "passive"))
      (node (ref "DD1") (pin "9") (pinfunction "VDDA/VREF+_9") (pintype "passive"))
    )
    (net (code "3") (name "+5B") (class "Default")
      (node (ref "C1") (pin "2") (pinfunction "2_2") (pintype "passive"))
      (node (ref "C13") (pin "2") (pinfunction "2_2") (pintype "passive"))
      (node (ref "C14") (pin "2") (pinfunction "2_2") (pintype "passive"))
      (node (ref "C15") (pin "2") (pinfunction "2_2") (pintype "passive"))
      (node (ref "C2") (pin "2") (pinfunction "2_2") (pintype "passive"))
      (node (ref "C29") (pin "2") (pinfunction "2_2") (pintype "passive"))
      (node (ref "C3") (pin "2") (pinfunction "2_2") (pintype "passive"))
      (node (ref "C30") (pin "2") (pinfunction "2_2") (pintype "passive"))
      (node (ref "C31") (pin "2") (pinfunction "2_2") (pintype "passive"))
      (node (ref "C41") (pin "2") (pinfunction "2_2") (pintype "passive"))
      (node (ref "C42") (pin "2") (pinfunction "2_2") (pintype "passive"))
      (node (ref "C43") (pin "2") (pinfunction "2_2") (pintype "passive"))
      (node (ref "C53") (pin "2") (pinfunction "2_2") (pintype "passive"))
      (node (ref "C54") (pin "2") (pinfunction "2_2") (pintype "passive"))
      (node (ref "C55") (pin "2") (pinfunction "2_2") (pintype "passive"))
      (node (ref "C65") (pin "2") (pinfunction "2_2") (pintype "passive"))
      (node (ref "C66") (pin "2") (pinfunction "2_2") (pintype "passive"))
      (node (ref "C67") (pin "2") (pinfunction "2_2") (pintype "passive"))
      (node (ref "DA12") (pin "3") (pinfunction "EN_3") (pintype "passive"))
      (node (ref "DA12") (pin "4") (pinfunction "VIN_4") (pintype "passive"))
      (node (ref "DA15") (pin "3") (pinfunction "EN_3") (pintype "passive"))
      (node (ref "DA15") (pin "4") (pinfunction "VIN_4") (pintype "passive"))
      (node (ref "DA18") (pin "3") (pinfunction "EN_3") (pintype "passive"))
      (node (ref "DA18") (pin "4") (pinfunction "VIN_4") (pintype "passive"))
      (node (ref "DA3") (pin "3") (pinfunction "EN_3") (pintype "passive"))
      (node (ref "DA3") (pin "4") (pinfunction "VIN_4") (pintype "passive"))
      (node (ref "DA6") (pin "3") (pinfunction "EN_3") (pintype "passive"))
      (node (ref "DA6") (pin "4") (pinfunction "VIN_4") (pintype "passive"))
      (node (ref "DA9") (pin "3") (pinfunction "EN_3") (pintype "passive"))
      (node (ref "DA9") (pin "4") (pinfunction "VIN_4") (pintype "passive"))
    )
    (net (code "4") (name "/AN_IN1") (class "Default")
      (node (ref "DA16") (pin "3") (pinfunction "AINP_3") (pintype "passive"))
    )
    (net (code "5") (name "/AN_IN2") (class "Default")
      (node (ref "DA13") (pin "3") (pinfunction "AINP_3") (pintype "passive"))
    )
    (net (code "6") (name "/AN_IN3") (class "Default")
      (node (ref "DA10") (pin "3") (pinfunction "AINP_3") (pintype "passive"))
    )
    (net (code "7") (name "/AN_IN4") (class "Default")
      (node (ref "DA7") (pin "3") (pinfunction "AINP_3") (pintype "passive"))
    )
    (net (code "8") (name "/AN_IN5") (class "Default")
      (node (ref "DA4") (pin "3") (pinfunction "AINP_3") (pintype "passive"))
    )
    (net (code "9") (name "/AN_IN6") (class "Default")
      (node (ref "DA1") (pin "3") (pinfunction "AINP_3") (pintype "passive"))
    )
    (net (code "10") (name "/CONVST_MCU") (class "Default")
      (node (ref "DA1") (pin "6") (pinfunction "CONVST_6") (pintype "passive"))
      (node (ref "DA10") (pin "6") (pinfunction "CONVST_6") (pintype "passive"))
      (node (ref "DA13") (pin "6") (pinfunction "CONVST_6") (pintype "passive"))
      (node (ref "DA16") (pin "6") (pinfunction "CONVST_6") (pintype "passive"))
      (node (ref "DA4") (pin "6") (pinfunction "CONVST_6") (pintype "passive"))
      (node (ref "DA7") (pin "6") (pinfunction "CONVST_6") (pintype "passive"))
      (node (ref "DD1") (pin "14") (pinfunction "PA4/SPI1_NSS/SPI3_NSS/USART2_CK/ADC12_IN4_14") (pintype "passive"))
      (node (ref "R4") (pin "2") (pinfunction "2_2") (pintype "passive"))
    )
    (net (code "11") (name "/SPI1_MISO_MCU") (class "Default")
      (node (ref "DA1") (pin "7") (pinfunction "DOUT_7") (pintype "passive"))
      (node (ref "DD1") (pin "16") (pinfunction "PA6/SPI1_MISO/ADC12_IN6/TIM3_CH1_(TIM1_BKIN)_16") (pintype "passive"))
    )
    (net (code "12") (name "/SPI1_SCLK_MCU") (class "Default")
      (node (ref "DA1") (pin "8") (pinfunction "SCLK_8") (pintype "passive"))
      (node (ref "DA10") (pin "8") (pinfunction "SCLK_8") (pintype "passive"))
      (node (ref "DA13") (pin "8") (pinfunction "SCLK_8") (pintype "passive"))
      (node (ref "DA16") (pin "8") (pinfunction "SCLK_8") (pintype "passive"))
      (node (ref "DA4") (pin "8") (pinfunction "SCLK_8") (pintype "passive"))
      (node (ref "DA7") (pin "8") (pinfunction "SCLK_8") (pintype "passive"))
      (node (ref "DD1") (pin "15") (pinfunction "PA5/SPI1_SCK/ADC12_IN5_15") (pintype "passive"))
    )
    (net (code "13") (name "AGND") (class "Default")
      (node (ref "C1") (pin "1") (pinfunction "1_1") (pintype "passive"))
      (node (ref "C10") (pin "1") (pinfunction "1_1") (pintype "passive"))
      (node (ref "C11") (pin "1") (pinfunction "1_1") (pintype "passive"))
      (node (ref "C12") (pin "1") (pinfunction "1_1") (pintype "passive"))
      (node (ref "C13") (pin "1") (pinfunction "1_1") (pintype "passive"))
      (node (ref "C14") (pin "1") (pinfunction "1_1") (pintype "passive"))
      (node (ref "C15") (pin "1") (pinfunction "1_1") (pintype "passive"))
      (node (ref "C16") (pin "1") (pinfunction "1_1") (pintype "passive"))
      (node (ref "C17") (pin "1") (pinfunction "1_1") (pintype "passive"))
      (node (ref "C18") (pin "1") (pinfunction "1_1") (pintype "passive"))
      (node (ref "C19") (pin "1") (pinfunction "1_1") (pintype "passive"))
      (node (ref "C2") (pin "1") (pinfunction "1_1") (pintype "passive"))
      (node (ref "C20") (pin "1") (pinfunction "1_1") (pintype "passive"))
      (node (ref "C21") (pin "1") (pinfunction "1_1") (pintype "passive"))
      (node (ref "C22") (pin "1") (pinfunction "1_1") (pintype "passive"))
      (node (ref "C23") (pin "1") (pinfunction "1_1") (pintype "passive"))
      (node (ref "C24") (pin "1") (pinfunction "1_1") (pintype "passive"))
      (node (ref "C29") (pin "1") (pinfunction "1_1") (pintype "passive"))
      (node (ref "C3") (pin "1") (pinfunction "1_1") (pintype "passive"))
      (node (ref "C30") (pin "1") (pinfunction "1_1") (pintype "passive"))
      (node (ref "C31") (pin "1") (pinfunction "1_1") (pintype "passive"))
      (node (ref "C32") (pin "1") (pinfunction "1_1") (pintype "passive"))
      (node (ref "C33") (pin "1") (pinfunction "1_1") (pintype "passive"))
      (node (ref "C34") (pin "1") (pinfunction "1_1") (pintype "passive"))
      (node (ref "C35") (pin "1") (pinfunction "1_1") (pintype "passive"))
      (node (ref "C36") (pin "1") (pinfunction "1_1") (pintype "passive"))
      (node (ref "C37") (pin "1") (pinfunction "1_1") (pintype "passive"))
      (node (ref "C38") (pin "1") (pinfunction "1_1") (pintype "passive"))
      (node (ref "C39") (pin "1") (pinfunction "1_1") (pintype "passive"))
      (node (ref "C4") (pin "1") (pinfunction "1_1") (pintype "passive"))
      (node (ref "C40") (pin "1") (pinfunction "1_1") (pintype "passive"))
      (node (ref "C41") (pin "1") (pinfunction "1_1") (pintype "passive"))
      (node (ref "C42") (pin "1") (pinfunction "1_1") (pintype "passive"))
      (node (ref "C43") (pin "1") (pinfunction "1_1") (pintype "passive"))
      (node (ref "C44") (pin "1") (pinfunction "1_1") (pintype "passive"))
      (node (ref "C45") (pin "1") (pinfunction "1_1") (pintype "passive"))
      (node (ref "C46") (pin "1") (pinfunction "1_1") (pintype "passive"))
      (node (ref "C47") (pin "1") (pinfunction "1_1") (pintype "passive"))
      (node (ref "C48") (pin "1") (pinfunction "1_1") (pintype "passive"))
      (node (ref "C49") (pin "1") (pinfunction "1_1") (pintype "passive"))
      (node (ref "C5") (pin "1") (pinfunction "1_1") (pintype "passive"))
      (node (ref "C50") (pin "1") (pinfunction "1_1") (pintype "passive"))
      (node (ref "C51") (pin "1") (pinfunction "1_1") (pintype "passive"))
      (node (ref "C52") (pin "1") (pinfunction "1_1") (pintype "passive"))
      (node (ref "C53") (pin "1") (pinfunction "1_1") (pintype "passive"))
      (node (ref "C54") (pin "1") (pinfunction "1_1") (pintype "passive"))
      (node (ref "C55") (pin "1") (pinfunction "1_1") (pintype "passive"))
      (node (ref "C56") (pin "1") (pinfunction "1_1") (pintype "passive"))
      (node (ref "C57") (pin "1") (pinfunction "1_1") (pintype "passive"))
      (node (ref "C58") (pin "1") (pinfunction "1_1") (pintype "passive"))
      (node (ref "C59") (pin "1") (pinfunction "1_1") (pintype "passive"))
      (node (ref "C6") (pin "1") (pinfunction "1_1") (pintype "passive"))
      (node (ref "C60") (pin "1") (pinfunction "1_1") (pintype "passive"))
      (node (ref "C61") (pin "1") (pinfunction "1_1") (pintype "passive"))
      (node (ref "C62") (pin "1") (pinfunction "1_1") (pintype "passive"))
      (node (ref "C63") (pin "1") (pinfunction "1_1") (pintype "passive"))
      (node (ref "C64") (pin "1") (pinfunction "1_1") (pintype "passive"))
      (node (ref "C65") (pin "1") (pinfunction "1_1") (pintype "passive"))
      (node (ref "C66") (pin "1") (pinfunction "1_1") (pintype "passive"))
      (node (ref "C67") (pin "1") (pinfunction "1_1") (pintype "passive"))
      (node (ref "C68") (pin "1") (pinfunction "1_1") (pintype "passive"))
      (node (ref "C69") (pin "1") (pinfunction "1_1") (pintype "passive"))
      (node (ref "C7") (pin "1") (pinfunction "1_1") (pintype "passive"))
      (node (ref "C70") (pin "1") (pinfunction "1_1") (pintype "passive"))
      (node (ref "C71") (pin "1") (pinfunction "1_1") (pintype "passive"))
      (node (ref "C72") (pin "1") (pinfunction "1_1") (pintype "passive"))
      (node (ref "C73") (pin "1") (pinfunction "1_1") (pintype "passive"))
      (node (ref "C74") (pin "1") (pinfunction "1_1") (pintype "passive"))
      (node (ref "C75") (pin "1") (pinfunction "1_1") (pintype "passive"))
      (node (ref "C76") (pin "1") (pinfunction "1_1") (pintype "passive"))
      (node (ref "C8") (pin "1") (pinfunction "1_1") (pintype "passive"))
      (node (ref "C9") (pin "1") (pinfunction "1_1") (pintype "passive"))
      (node (ref "DA1") (pin "4") (pinfunction "AINN_4") (pintype "passive"))
      (node (ref "DA1") (pin "5") (pinfunction "GND_5") (pintype "passive"))
      (node (ref "DA10") (pin "4") (pinfunction "AINN_4") (pintype "passive"))
      (node (ref "DA10") (pin "5") (pinfunction "GND_5") (pintype "passive"))
      (node (ref "DA11") (pin "2") (pinfunction "V-_2") (pintype "passive"))
      (node (ref "DA12") (pin "2") (pinfunction "GND_2") (pintype "passive"))
      (node (ref "DA13") (pin "4") (pinfunction "AINN_4") (pintype "passive"))
      (node (ref "DA13") (pin "5") (pinfunction "GND_5") (pintype "passive"))
      (node (ref "DA14") (pin "2") (pinfunction "V-_2") (pintype "passive"))
      (node (ref "DA15") (pin "2") (pinfunction "GND_2") (pintype "passive"))
      (node (ref "DA16") (pin "4") (pinfunction "AINN_4") (pintype "passive"))
      (node (ref "DA16") (pin "5") (pinfunction "GND_5") (pintype "passive"))
      (node (ref "DA16") (pin "9") (pinfunction "DIN_9") (pintype "passive"))
      (node (ref "DA17") (pin "2") (pinfunction "V-_2") (pintype "passive"))
      (node (ref "DA18") (pin "2") (pinfunction "GND_2") (pintype "passive"))
      (node (ref "DA2") (pin "2") (pinfunction "V-_2") (pintype "passive"))
      (node (ref "DA3") (pin "2") (pinfunction "GND_2") (pintype "passive"))
      (node (ref "DA4") (pin "4") (pinfunction "AINN_4") (pintype "passive"))
      (node (ref "DA4") (pin "5") (pinfunction "GND_5") (pintype "passive"))
      (node (ref "DA5") (pin "2") (pinfunction "V-_2") (pintype "passive"))
      (node (ref "DA6") (pin "2") (pinfunction "GND_2") (pintype "passive"))
      (node (ref "DA7") (pin "4") (pinfunction "AINN_4") (pintype "passive"))
      (node (ref "DA7") (pin "5") (pinfunction "GND_5") (pintype "passive"))
      (node (ref "DA8") (pin "2") (pinfunction "V-_2") (pintype "passive"))
      (node (ref "DA9") (pin "2") (pinfunction "GND_2") (pintype "passive"))
    )
    (net (code "14") (name "DGND") (class "Default")
      (node (ref "C25") (pin "1") (pinfunction "1_1") (pintype "passive"))
      (node (ref "C26") (pin "1") (pinfunction "1_1") (pintype "passive"))
      (node (ref "C27") (pin "1") (pinfunction "1_1") (pintype "passive"))
      (node (ref "C28") (pin "1") (pinfunction "1_1") (pintype "passive"))
      (node (ref "DD1") (pin "23") (pinfunction "VSS_1_23") (pintype "passive"))
      (node (ref "DD1") (pin "35") (pinfunction "VSS_2_35") (pintype "passive"))
      (node (ref "DD1") (pin "47") (pinfunction "VSS_3_47") (pintype "passive"))
      (node (ref "DD1") (pin "8") (pinfunction "VSSA/VREF-_8") (pintype "passive"))
      (node (ref "R4") (pin "1") (pinfunction "1_1") (pintype "passive"))
    )
    (net (code "15") (name "Net-(C5-Pad2)") (class "Default")
      (node (ref "C5") (pin "2") (pinfunction "2_2") (pintype "passive"))
      (node (ref "C6") (pin "2") (pinfunction "2_2") (pintype "passive"))
      (node (ref "R2") (pin "1") (pinfunction "1_1") (pintype "passive"))
    )
    (net (code "16") (name "Net-(C17-Pad2)") (class "Default")
      (node (ref "C17") (pin "2") (pinfunction "2_2") (pintype "passive"))
      (node (ref "C18") (pin "2") (pinfunction "2_2") (pintype "passive"))
      (node (ref "R6") (pin "1") (pinfunction "1_1") (pintype "passive"))
    )
    (net (code "17") (name "Net-(C33-Pad2)") (class "Default")
      (node (ref "C33") (pin "2") (pinfunction "2_2") (pintype "passive"))
      (node (ref "C34") (pin "2") (pinfunction "2_2") (pintype "passive"))
      (node (ref "R9") (pin "1") (pinfunction "1_1") (pintype "passive"))
    )
    (net (code "18") (name "Net-(C45-Pad2)") (class "Default")
      (node (ref "C45") (pin "2") (pinfunction "2_2") (pintype "passive"))
      (node (ref "C46") (pin "2") (pinfunction "2_2") (pintype "passive"))
      (node (ref "R12") (pin "1") (pinfunction "1_1") (pintype "passive"))
    )
    (net (code "19") (name "Net-(C57-Pad2)") (class "Default")
      (node (ref "C57") (pin "2") (pinfunction "2_2") (pintype "passive"))
      (node (ref "C58") (pin "2") (pinfunction "2_2") (pintype "passive"))
      (node (ref "R15") (pin "1") (pinfunction "1_1") (pintype "passive"))
    )
    (net (code "20") (name "Net-(C69-Pad2)") (class "Default")
      (node (ref "C69") (pin "2") (pinfunction "2_2") (pintype "passive"))
      (node (ref "C70") (pin "2") (pinfunction "2_2") (pintype "passive"))
      (node (ref "R18") (pin "1") (pinfunction "1_1") (pintype "passive"))
    )
    (net (code "21") (name "Net-(DA1-DIN)") (class "Default")
      (node (ref "DA1") (pin "9") (pinfunction "DIN_9") (pintype "passive"))
      (node (ref "DA4") (pin "7") (pinfunction "DOUT_7") (pintype "passive"))
    )
    (net (code "22") (name "Net-(DA1-REF)") (class "Default")
      (node (ref "DA1") (pin "1") (pinfunction "REF_1") (pintype "passive"))
      (node (ref "R1") (pin "2") (pinfunction "2_2") (pintype "passive"))
      (node (ref "R2") (pin "2") (pinfunction "2_2") (pintype "passive"))
    )
    (net (code "23") (name "Net-(DA2-+IN)") (class "Default")
      (node (ref "C4") (pin "2") (pinfunction "2_2") (pintype "passive"))
      (node (ref "DA2") (pin "3") (pinfunction "+IN_3") (pintype "passive"))
      (node (ref "R3") (pin "2") (pinfunction "2_2") (pintype "passive"))
    )
    (net (code "24") (name "Net-(DA2--IN)") (class "Default")
      (node (ref "DA2") (pin "1") (pinfunction "OUT_1") (pintype "passive"))
      (node (ref "DA2") (pin "4") (pinfunction "-IN_4") (pintype "passive"))
      (node (ref "R1") (pin "1") (pinfunction "1_1") (pintype "passive"))
    )
    (net (code "25") (name "Net-(DA3-Vref)") (class "Default")
      (node (ref "DA3") (pin "5") (pinfunction "Vref_5") (pintype "passive"))
      (node (ref "R3") (pin "1") (pinfunction "1_1") (pintype "passive"))
    )
    (net (code "26") (name "Net-(DA4-DIN)") (class "Default")
      (node (ref "DA4") (pin "9") (pinfunction "DIN_9") (pintype "passive"))
      (node (ref "DA7") (pin "7") (pinfunction "DOUT_7") (pintype "passive"))
    )
    (net (code "27") (name "Net-(DA4-REF)") (class "Default")
      (node (ref "DA4") (pin "1") (pinfunction "REF_1") (pintype "passive"))
      (node (ref "R5") (pin "2") (pinfunction "2_2") (pintype "passive"))
      (node (ref "R6") (pin "2") (pinfunction "2_2") (pintype "passive"))
    )
    (net (code "28") (name "Net-(DA5-+IN)") (class "Default")
      (node (ref "C16") (pin "2") (pinfunction "2_2") (pintype "passive"))
      (node (ref "DA5") (pin "3") (pinfunction "+IN_3") (pintype "passive"))
      (node (ref "R7") (pin "2") (pinfunction "2_2") (pintype "passive"))
    )
    (net (code "29") (name "Net-(DA5--IN)") (class "Default")
      (node (ref "DA5") (pin "1") (pinfunction "OUT_1") (pintype "passive"))
      (node (ref "DA5") (pin "4") (pinfunction "-IN_4") (pintype "passive"))
      (node (ref "R5") (pin "1") (pinfunction "1_1") (pintype "passive"))
    )
    (net (code "30") (name "Net-(DA6-Vref)") (class "Default")
      (node (ref "DA6") (pin "5") (pinfunction "Vref_5") (pintype "passive"))
      (node (ref "R7") (pin "1") (pinfunction "1_1") (pintype "passive"))
    )
    (net (code "31") (name "Net-(DA7-REF)") (class "Default")
      (node (ref "DA7") (pin "1") (pinfunction "REF_1") (pintype "passive"))
      (node (ref "R8") (pin "2") (pinfunction "2_2") (pintype "passive"))
      (node (ref "R9") (pin "2") (pinfunction "2_2") (pintype "passive"))
    )
    (net (code "32") (name "Net-(DA8-+IN)") (class "Default")
      (node (ref "C32") (pin "2") (pinfunction "2_2") (pintype "passive"))
      (node (ref "DA8") (pin "3") (pinfunction "+IN_3") (pintype "passive"))
      (node (ref "R10") (pin "2") (pinfunction "2_2") (pintype "passive"))
    )
    (net (code "33") (name "Net-(DA8--IN)") (class "Default")
      (node (ref "DA8") (pin "1") (pinfunction "OUT_1") (pintype "passive"))
      (node (ref "DA8") (pin "4") (pinfunction "-IN_4") (pintype "passive"))
      (node (ref "R8") (pin "1") (pinfunction "1_1") (pintype "passive"))
    )
    (net (code "34") (name "Net-(DA9-Vref)") (class "Default")
      (node (ref "DA9") (pin "5") (pinfunction "Vref_5") (pintype "passive"))
      (node (ref "R10") (pin "1") (pinfunction "1_1") (pintype "passive"))
    )
    (net (code "35") (name "Net-(DA10-DIN)") (class "Default")
      (node (ref "DA10") (pin "9") (pinfunction "DIN_9") (pintype "passive"))
      (node (ref "DA13") (pin "7") (pinfunction "DOUT_7") (pintype "passive"))
    )
    (net (code "36") (name "Net-(DA10-DOUT)") (class "Default")
      (node (ref "DA10") (pin "7") (pinfunction "DOUT_7") (pintype "passive"))
      (node (ref "DA7") (pin "9") (pinfunction "DIN_9") (pintype "passive"))
    )
    (net (code "37") (name "Net-(DA10-REF)") (class "Default")
      (node (ref "DA10") (pin "1") (pinfunction "REF_1") (pintype "passive"))
      (node (ref "R11") (pin "2") (pinfunction "2_2") (pintype "passive"))
      (node (ref "R12") (pin "2") (pinfunction "2_2") (pintype "passive"))
    )
    (net (code "38") (name "Net-(DA11-+IN)") (class "Default")
      (node (ref "C44") (pin "2") (pinfunction "2_2") (pintype "passive"))
      (node (ref "DA11") (pin "3") (pinfunction "+IN_3") (pintype "passive"))
      (node (ref "R13") (pin "2") (pinfunction "2_2") (pintype "passive"))
    )
    (net (code "39") (name "Net-(DA11--IN)") (class "Default")
      (node (ref "DA11") (pin "1") (pinfunction "OUT_1") (pintype "passive"))
      (node (ref "DA11") (pin "4") (pinfunction "-IN_4") (pintype "passive"))
      (node (ref "R11") (pin "1") (pinfunction "1_1") (pintype "passive"))
    )
    (net (code "40") (name "Net-(DA12-Vref)") (class "Default")
      (node (ref "DA12") (pin "5") (pinfunction "Vref_5") (pintype "passive"))
      (node (ref "R13") (pin "1") (pinfunction "1_1") (pintype "passive"))
    )
    (net (code "41") (name "Net-(DA13-DIN)") (class "Default")
      (node (ref "DA13") (pin "9") (pinfunction "DIN_9") (pintype "passive"))
      (node (ref "DA16") (pin "7") (pinfunction "DOUT_7") (pintype "passive"))
    )
    (net (code "42") (name "Net-(DA13-REF)") (class "Default")
      (node (ref "DA13") (pin "1") (pinfunction "REF_1") (pintype "passive"))
      (node (ref "R14") (pin "2") (pinfunction "2_2") (pintype "passive"))
      (node (ref "R15") (pin "2") (pinfunction "2_2") (pintype "passive"))
    )
    (net (code "43") (name "Net-(DA14-+IN)") (class "Default")
      (node (ref "C56") (pin "2") (pinfunction "2_2") (pintype "passive"))
      (node (ref "DA14") (pin "3") (pinfunction "+IN_3") (pintype "passive"))
      (node (ref "R16") (pin "2") (pinfunction "2_2") (pintype "passive"))
    )
    (net (code "44") (name "Net-(DA14--IN)") (class "Default")
      (node (ref "DA14") (pin "1") (pinfunction "OUT_1") (pintype "passive"))
      (node (ref "DA14") (pin "4") (pinfunction "-IN_4") (pintype "passive"))
      (node (ref "R14") (pin "1") (pinfunction "1_1") (pintype "passive"))
    )
    (net (code "45") (name "Net-(DA15-Vref)") (class "Default")
      (node (ref "DA15") (pin "5") (pinfunction "Vref_5") (pintype "passive"))
      (node (ref "R16") (pin "1") (pinfunction "1_1") (pintype "passive"))
    )
    (net (code "46") (name "Net-(DA16-REF)") (class "Default")
      (node (ref "DA16") (pin "1") (pinfunction "REF_1") (pintype "passive"))
      (node (ref "R17") (pin "2") (pinfunction "2_2") (pintype "passive"))
      (node (ref "R18") (pin "2") (pinfunction "2_2") (pintype "passive"))
    )
    (net (code "47") (name "Net-(DA17-+IN)") (class "Default")
      (node (ref "C68") (pin "2") (pinfunction "2_2") (pintype "passive"))
      (node (ref "DA17") (pin "3") (pinfunction "+IN_3") (pintype "passive"))
      (node (ref "R19") (pin "2") (pinfunction "2_2") (pintype "passive"))
    )
    (net (code "48") (name "Net-(DA17--IN)") (class "Default")
      (node (ref "DA17") (pin "1") (pinfunction "OUT_1") (pintype "passive"))
      (node (ref "DA17") (pin "4") (pinfunction "-IN_4") (pintype "passive"))
      (node (ref "R17") (pin "1") (pinfunction "1_1") (pintype "passive"))
    )
    (net (code "49") (name "Net-(DA18-Vref)") (class "Default")
      (node (ref "DA18") (pin "5") (pinfunction "Vref_5") (pintype "passive"))
      (node (ref "R19") (pin "1") (pinfunction "1_1") (pintype "passive"))
    )
    (net (code "50") (name "unconnected-(DA3-N{slash}C-Pad1)") (class "Default")
      (node (ref "DA3") (pin "1") (pinfunction "N/C_1") (pintype "passive+no_connect"))
    )
    (net (code "51") (name "unconnected-(DA6-N{slash}C-Pad1)") (class "Default")
      (node (ref "DA6") (pin "1") (pinfunction "N/C_1") (pintype "passive+no_connect"))
    )
    (net (code "52") (name "unconnected-(DA9-N{slash}C-Pad1)") (class "Default")
      (node (ref "DA9") (pin "1") (pinfunction "N/C_1") (pintype "passive+no_connect"))
    )
    (net (code "53") (name "unconnected-(DA12-N{slash}C-Pad1)") (class "Default")
      (node (ref "DA12") (pin "1") (pinfunction "N/C_1") (pintype "passive+no_connect"))
    )
    (net (code "54") (name "unconnected-(DA15-N{slash}C-Pad1)") (class "Default")
      (node (ref "DA15") (pin "1") (pinfunction "N/C_1") (pintype "passive+no_connect"))
    )
    (net (code "55") (name "unconnected-(DA18-N{slash}C-Pad1)") (class "Default")
      (node (ref "DA18") (pin "1") (pinfunction "N/C_1") (pintype "passive+no_connect"))
    )
    (net (code "56") (name "unconnected-(DD1-BOOT0-Pad44)") (class "Default")
      (node (ref "DD1") (pin "44") (pinfunction "BOOT0_44") (pintype "passive"))
    )
    (net (code "57") (name "unconnected-(DD1-FT_JTDO_(SPI1_SCK{slash}TIM2_CH2{slash}TRACESWO{slash}PB3)-Pad39)") (class "Default")
      (node (ref "DD1") (pin "39") (pinfunction "FT_JTDO_(SPI1_SCK/TIM2_CH2/TRACESWO/PB3)_39") (pintype "passive"))
    )
    (net (code "58") (name "unconnected-(DD1-FT_NJTRST_(SPI1_MISO{slash}TIM3_CH1{slash}PB4)-Pad40)") (class "Default")
      (node (ref "DD1") (pin "40") (pinfunction "FT_NJTRST_(SPI1_MISO/TIM3_CH1/PB4)_40") (pintype "passive"))
    )
    (net (code "59") (name "unconnected-(DD1-FT_PB6{slash}I2C1_SCL{slash}TIM4_CH1_(USART1_TX)-Pad42)") (class "Default")
      (node (ref "DD1") (pin "42") (pinfunction "FT_PB6/I2C1_SCL/TIM4_CH1_(USART1_TX)_42") (pintype "passive"))
    )
    (net (code "60") (name "unconnected-(DD1-FT_PB7{slash}I2C1_SDA{slash}TIM4_CH2_(USART1_RX)-Pad43)") (class "Default")
      (node (ref "DD1") (pin "43") (pinfunction "FT_PB7/I2C1_SDA/TIM4_CH2_(USART1_RX)_43") (pintype "passive"))
    )
    (net (code "61") (name "unconnected-(DD1-FT_PB8{slash}TIM4_CH3_(I2C1_SCL{slash}CANRX)-Pad45)") (class "Default")
      (node (ref "DD1") (pin "45") (pinfunction "FT_PB8/TIM4_CH3_(I2C1_SCL/CANRX)_45") (pintype "passive"))
    )
    (net (code "62") (name "unconnected-(DD1-FT_PB9{slash}TIM4_CH4_(I2C1_SDA{slash}CANTX)-Pad46)") (class "Default")
      (node (ref "DD1") (pin "46") (pinfunction "FT_PB9/TIM4_CH4_(I2C1_SDA/CANTX)_46") (pintype "passive"))
    )
    (net (code "63") (name "unconnected-(DD1-FT_PB10{slash}USART3_TX{slash}I2C2_SCL_(TIM2_CH3)-Pad21)") (class "Default")
      (node (ref "DD1") (pin "21") (pinfunction "FT_PB10/USART3_TX/I2C2_SCL_(TIM2_CH3)_21") (pintype "passive"))
    )
    (net (code "64") (name "unconnected-(DD1-FT_PB11{slash}I2S2_SDA{slash}USART3_RX_(TIM2_CH4)-Pad22)") (class "Default")
      (node (ref "DD1") (pin "22") (pinfunction "FT_PB11/I2S2_SDA/USART3_RX_(TIM2_CH4)_22") (pintype "passive"))
    )
    (net (code "65") (name "unconnected-(DD1-FT_PB12{slash}SPI2_NSS{slash}I2C2_SMBAI{slash}USART3_CK{slash}TIM1_BKIN-Pad25)") (class "Default")
      (node (ref "DD1") (pin "25") (pinfunction "FT_PB12/SPI2_NSS/I2C2_SMBAI/USART3_CK/TIM1_BKIN_25") (pintype "passive"))
    )
    (net (code "66") (name "unconnected-(DD1-FT_PB13{slash}SPI2_SCK{slash}USART3_CTS{slash}TIM1_CH1N-Pad26)") (class "Default")
      (node (ref "DD1") (pin "26") (pinfunction "FT_PB13/SPI2_SCK/USART3_CTS/TIM1_CH1N_26") (pintype "passive"))
    )
    (net (code "67") (name "unconnected-(DD1-FT_PB14{slash}SPI2_MISO{slash}USART3_RTS{slash}TIM1_CH2N-Pad27)") (class "Default")
      (node (ref "DD1") (pin "27") (pinfunction "FT_PB14/SPI2_MISO/USART3_RTS/TIM1_CH2N_27") (pintype "passive"))
    )
    (net (code "68") (name "unconnected-(DD1-FT_PB15{slash}SPI2_MOSI{slash}TIM1_CH3N-Pad28)") (class "Default")
      (node (ref "DD1") (pin "28") (pinfunction "FT_PB15/SPI2_MOSI/TIM1_CH3N_28") (pintype "passive"))
    )
    (net (code "69") (name "unconnected-(DD1-JTCK{slash}SWCLK_(PA14)_FT-Pad37)") (class "Default")
      (node (ref "DD1") (pin "37") (pinfunction "JTCK/SWCLK_(PA14)_FT_37") (pintype "passive"))
    )
    (net (code "70") (name "unconnected-(DD1-JTDI_(SPI1_NSS{slash}TIM2_CH1_ETR{slash}PA15)_FT-Pad38)") (class "Default")
      (node (ref "DD1") (pin "38") (pinfunction "JTDI_(SPI1_NSS/TIM2_CH1_ETR/PA15)_FT_38") (pintype "passive"))
    )
    (net (code "71") (name "unconnected-(DD1-JTMS{slash}SWDIO_(PA13)_FT-Pad34)") (class "Default")
      (node (ref "DD1") (pin "34") (pinfunction "JTMS/SWDIO_(PA13)_FT_34") (pintype "passive"))
    )
    (net (code "72") (name "unconnected-(DD1-NRST-Pad7)") (class "Default")
      (node (ref "DD1") (pin "7") (pinfunction "NRST_7") (pintype "passive"))
    )
    (net (code "73") (name "unconnected-(DD1-OSC_IN_(PDO)-Pad5)") (class "Default")
      (node (ref "DD1") (pin "5") (pinfunction "OSC_IN_(PDO)_5") (pintype "passive"))
    )
    (net (code "74") (name "unconnected-(DD1-OSC_OUT_(PD1)-Pad6)") (class "Default")
      (node (ref "DD1") (pin "6") (pinfunction "OSC_OUT_(PD1)_6") (pintype "passive"))
    )
    (net (code "75") (name "unconnected-(DD1-PA0{slash}WKUP{slash}USART2_CTS{slash}ADC12_IN0{slash}TIM2_CH1_ETR-Pad10)") (class "Default")
      (node (ref "DD1") (pin "10") (pinfunction "PA0/WKUP/USART2_CTS/ADC12_IN0/TIM2_CH1_ETR_10") (pintype "passive"))
    )
    (net (code "76") (name "unconnected-(DD1-PA1{slash}USART2_RTS{slash}TIM2_CH2{slash}ADC12_IN1-Pad11)") (class "Default")
      (node (ref "DD1") (pin "11") (pinfunction "PA1/USART2_RTS/TIM2_CH2/ADC12_IN1_11") (pintype "passive"))
    )
    (net (code "77") (name "unconnected-(DD1-PA2{slash}USART2_TX{slash}TIM2_CH3{slash}ADC12_IN2-Pad12)") (class "Default")
      (node (ref "DD1") (pin "12") (pinfunction "PA2/USART2_TX/TIM2_CH3/ADC12_IN2_12") (pintype "passive"))
    )
    (net (code "78") (name "unconnected-(DD1-PA3{slash}USART2_RX{slash}TIM2_CH4{slash}ADC12_IN3-Pad13)") (class "Default")
      (node (ref "DD1") (pin "13") (pinfunction "PA3/USART2_RX/TIM2_CH4/ADC12_IN3_13") (pintype "passive"))
    )
    (net (code "79") (name "unconnected-(DD1-PA7{slash}SPI1_MOSI{slash}ADC12_IN7{slash}TIM3_CH2_(TIM1_CH1N)-Pad17)") (class "Default")
      (node (ref "DD1") (pin "17") (pinfunction "PA7/SPI1_MOSI/ADC12_IN7/TIM3_CH2_(TIM1_CH1N)_17") (pintype "passive"))
    )
    (net (code "80") (name "unconnected-(DD1-PA8{slash}USART1_CK{slash}TIM1_CH1{slash}MCO_FT-Pad29)") (class "Default")
      (node (ref "DD1") (pin "29") (pinfunction "PA8/USART1_CK/TIM1_CH1/MCO_FT_29") (pintype "passive"))
    )
    (net (code "81") (name "unconnected-(DD1-PA9{slash}USART1_TX{slash}TIM1_CH2_FT-Pad30)") (class "Default")
      (node (ref "DD1") (pin "30") (pinfunction "PA9/USART1_TX/TIM1_CH2_FT_30") (pintype "passive"))
    )
    (net (code "82") (name "unconnected-(DD1-PA10{slash}USART1_RX{slash}TIM1_CH3_FT-Pad31)") (class "Default")
      (node (ref "DD1") (pin "31") (pinfunction "PA10/USART1_RX/TIM1_CH3_FT_31") (pintype "passive"))
    )
    (net (code "83") (name "unconnected-(DD1-PA11{slash}USART1_CTS{slash}CANRX{slash}USBDM{slash}TIM1_CH4_FT-Pad32)") (class "Default")
      (node (ref "DD1") (pin "32") (pinfunction "PA11/USART1_CTS/CANRX/USBDM/TIM1_CH4_FT_32") (pintype "passive"))
    )
    (net (code "84") (name "unconnected-(DD1-PA12{slash}USART1_RTS{slash}USART6_RX{slash}CANTX{slash}USBDP{slash}TIM1_ETR_FT-Pad33)") (class "Default")
      (node (ref "DD1") (pin "33") (pinfunction "PA12/USART1_RTS/USART6_RX/CANTX/USBDP/TIM1_ETR_FT_33") (pintype "passive"))
    )
    (net (code "85") (name "unconnected-(DD1-PB0{slash}ADC12_IN8{slash}TIM3_CH3_(TIM1_CH2N)-Pad18)") (class "Default")
      (node (ref "DD1") (pin "18") (pinfunction "PB0/ADC12_IN8/TIM3_CH3_(TIM1_CH2N)_18") (pintype "passive"))
    )
    (net (code "86") (name "unconnected-(DD1-PB1{slash}TIM3_CH4T{slash}ADC12_IN9_(TIM1_CH3N)-Pad19)") (class "Default")
      (node (ref "DD1") (pin "19") (pinfunction "PB1/TIM3_CH4T/ADC12_IN9_(TIM1_CH3N)_19") (pintype "passive"))
    )
    (net (code "87") (name "unconnected-(DD1-PB2{slash}BOOT1-Pad20)") (class "Default")
      (node (ref "DD1") (pin "20") (pinfunction "PB2/BOOT1_20") (pintype "passive"))
    )
    (net (code "88") (name "unconnected-(DD1-PB5{slash}I2C1_SMBAI_(TIM3_CH2{slash}SPI1_MOSI)-Pad41)") (class "Default")
      (node (ref "DD1") (pin "41") (pinfunction "PB5/I2C1_SMBAI_(TIM3_CH2/SPI1_MOSI)_41") (pintype "passive"))
    )
    (net (code "89") (name "unconnected-(DD1-PC13-TAMPER-RTC-Pad2)") (class "Default")
      (node (ref "DD1") (pin "2") (pinfunction "PC13-TAMPER-RTC_2") (pintype "passive"))
    )
    (net (code "90") (name "unconnected-(DD1-PC14-OSC32_IN-Pad3)") (class "Default")
      (node (ref "DD1") (pin "3") (pinfunction "PC14-OSC32_IN_3") (pintype "passive"))
    )
    (net (code "91") (name "unconnected-(DD1-PC15-OSC32_OUT-Pad4)") (class "Default")
      (node (ref "DD1") (pin "4") (pinfunction "PC15-OSC32_OUT_4") (pintype "passive"))
    )
    (net (code "92") (name "unconnected-(DD1-VBAT-Pad1)") (class "Default")
      (node (ref "DD1") (pin "1") (pinfunction "VBAT_1") (pintype "passive"))
    )
  )
)
